# rapidshark-lipo-sensor-mk-2_1.net
KiCad netlist of a schematic drawn in EAGLE
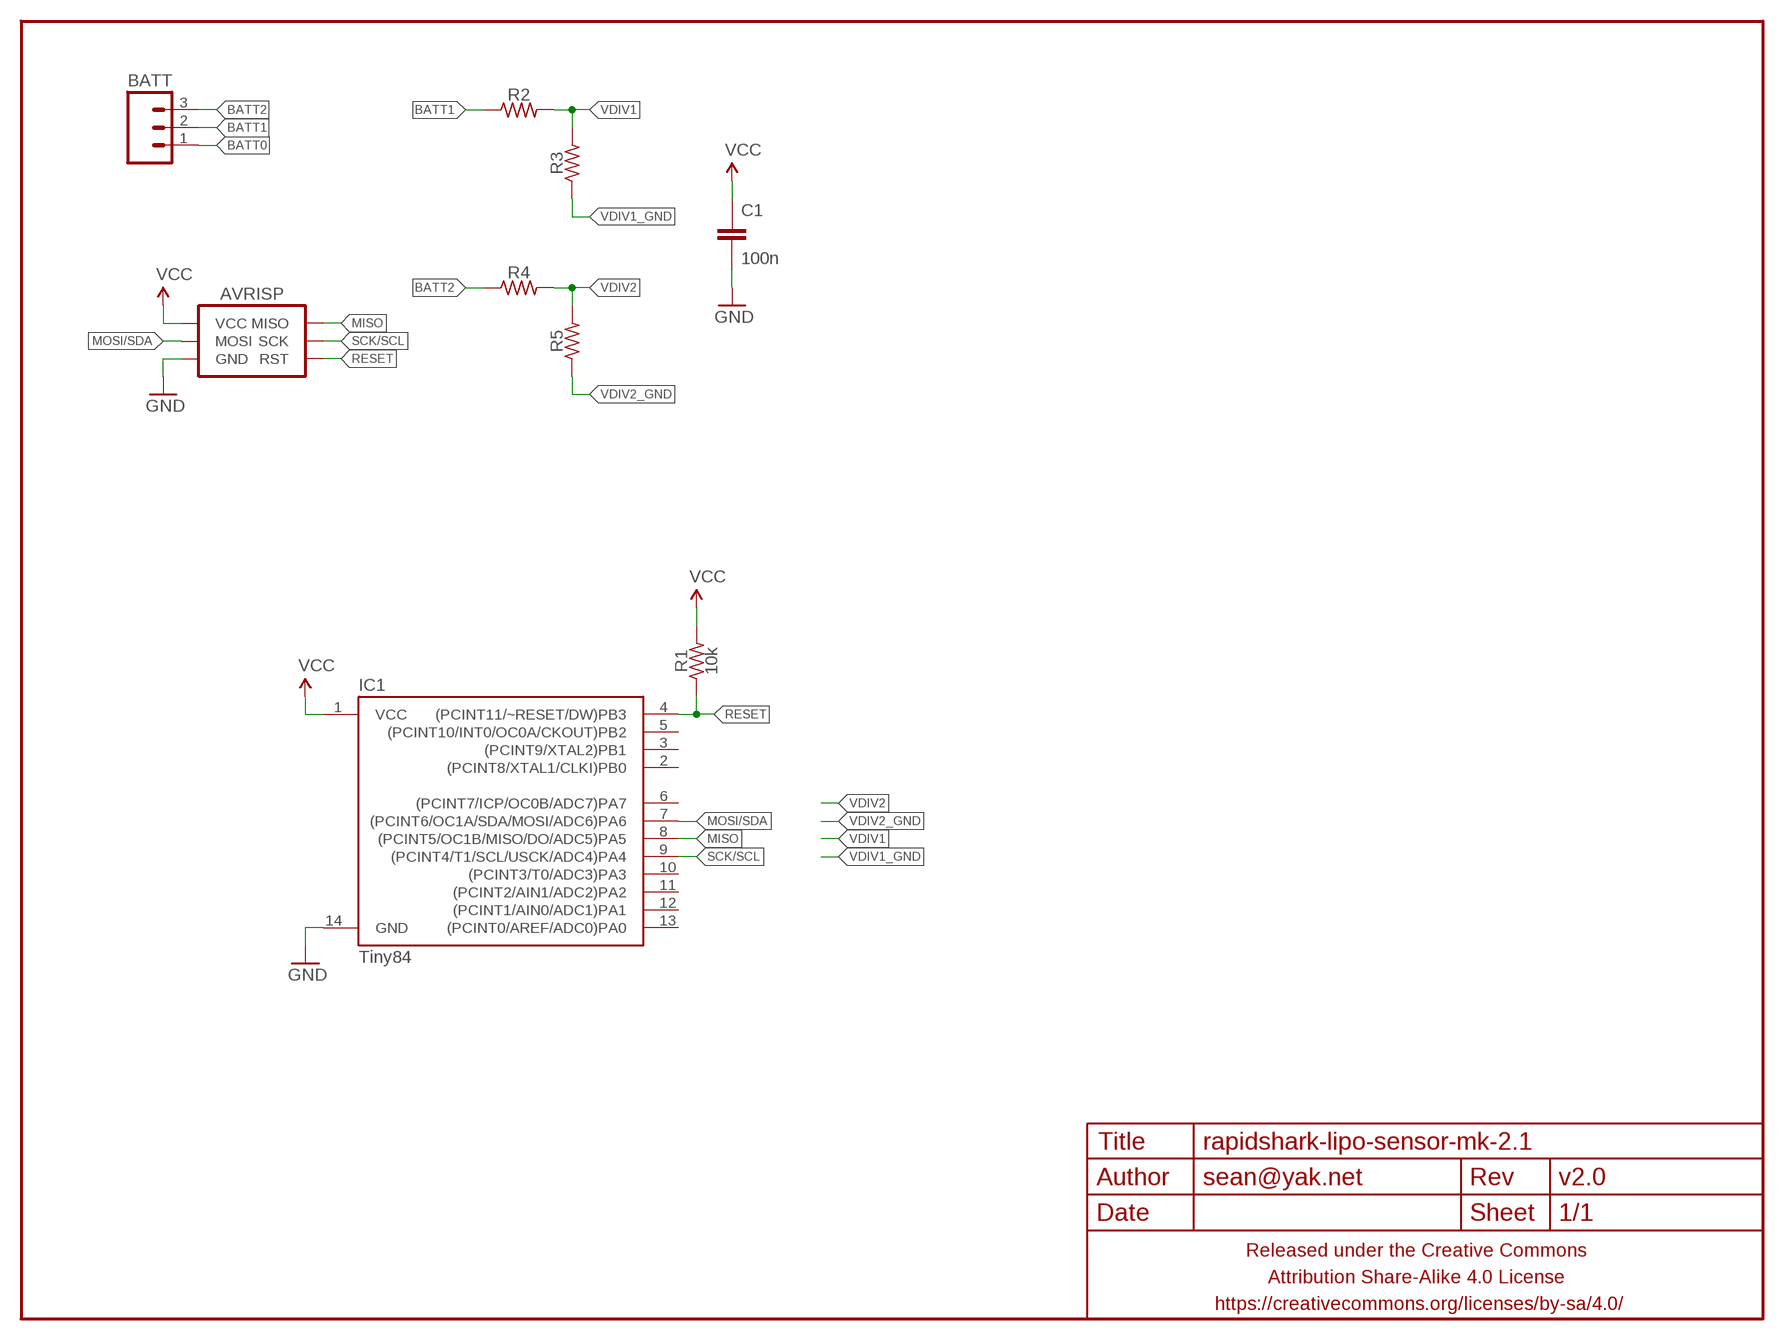
[diagram p0: schematic, sheet 1]

(export (version "E")
  (design (tool "Eeschema 10.0.6"))
  (components
    (comp (ref "AVRISP")
      (value "AVR_SPI_PRG_6PTH_INLINE_I2C")
      (footprint "eagle-import:AVR_ISP_INLINE_PTH_I2C")
      (libsource (lib "eagle-import") (part "AVR_SPI_PRG_6PTH_INLINE_I2C"))
    )
    (comp (ref "BATT")
      (value "M03PTH-CENTERED")
      (footprint "eagle-import:1X03-CENTERED")
      (libsource (lib "eagle-import") (part "M03PTH-CENTERED"))
    )
    (comp (ref "C1")
      (value "100n")
      (footprint "eagle-import:C025-024X044")
      (libsource (lib "eagle-import") (part "CAPACITOR-CERAMIC025-024X044"))
    )
    (comp (ref "FRAME1")
      (value "FRAME-LETTERNO_PACKAGE")
      (footprint "eagle-import:DUMMY")
      (fields (field (name "DESIGNER") "sean@yak.net") (field (name "VERSION") "v2.0"))
      (libsource (lib "eagle-import") (part "FRAME-LETTERNO_PACKAGE"))
    )
    (comp (ref "IC1")
      (value "Tiny84")
      (footprint "eagle-import:DIL14")
      (libsource (lib "eagle-import") (part "ATTINY84ATTINY84-20PU"))
    )
    (comp (ref "R1")
      (value "10k")
      (footprint "eagle-import:RESISTOR-AXIAL-PTH-5.08MM")
      (libsource (lib "eagle-import") (part "RESISTORPTH-AXIAL-5.08MM"))
    )
    (comp (ref "R2")
      (value "RESISTORPTH-AXIAL-5.08MM")
      (footprint "eagle-import:RESISTOR-AXIAL-PTH-5.08MM")
      (libsource (lib "eagle-import") (part "RESISTORPTH-AXIAL-5.08MM"))
    )
    (comp (ref "R3")
      (value "RESISTORPTH-AXIAL-5.08MM")
      (footprint "eagle-import:RESISTOR-AXIAL-PTH-5.08MM")
      (libsource (lib "eagle-import") (part "RESISTORPTH-AXIAL-5.08MM"))
    )
    (comp (ref "R4")
      (value "RESISTORPTH-AXIAL-5.08MM")
      (footprint "eagle-import:RESISTOR-AXIAL-PTH-5.08MM")
      (libsource (lib "eagle-import") (part "RESISTORPTH-AXIAL-5.08MM"))
    )
    (comp (ref "R5")
      (value "RESISTORPTH-AXIAL-5.08MM")
      (footprint "eagle-import:RESISTOR-AXIAL-PTH-5.08MM")
      (libsource (lib "eagle-import") (part "RESISTORPTH-AXIAL-5.08MM"))
    )
  )
  (nets
    (net (code "1") (name "BATT0") (class "Default")
      (node (ref "BATT") (pin "1") (pinfunction "1_1") (pintype "passive"))
    )
    (net (code "2") (name "BATT1") (class "Default")
      (node (ref "BATT") (pin "2") (pinfunction "2_2") (pintype "passive"))
      (node (ref "R2") (pin "P$1") (pinfunction "1_P$1") (pintype "passive"))
    )
    (net (code "3") (name "BATT2") (class "Default")
      (node (ref "BATT") (pin "3") (pinfunction "3_3") (pintype "passive"))
      (node (ref "R4") (pin "P$1") (pinfunction "1_P$1") (pintype "passive"))
    )
    (net (code "4") (name "GND") (class "Default")
      (node (ref "AVRISP") (pin "GND") (pinfunction "GND_GND") (pintype "passive"))
      (node (ref "C1") (pin "2") (pinfunction "2_2") (pintype "passive"))
      (node (ref "IC1") (pin "14") (pinfunction "GND_14") (pintype "bidirectional"))
    )
    (net (code "5") (name "MISO") (class "Default")
      (node (ref "AVRISP") (pin "MISO") (pinfunction "MISO_MISO") (pintype "passive"))
      (node (ref "IC1") (pin "8") (pinfunction "(PCINT5/OC1B/MISO/DO/ADC5)PA5_8") (pintype "bidirectional"))
    )
    (net (code "6") (name "MOSI{slash}SDA") (class "Default")
      (node (ref "AVRISP") (pin "MOSI") (pinfunction "MOSI_MOSI") (pintype "passive"))
      (node (ref "IC1") (pin "7") (pinfunction "(PCINT6/OC1A/SDA/MOSI/ADC6)PA6_7") (pintype "bidirectional"))
    )
    (net (code "7") (name "RESET") (class "Default")
      (node (ref "AVRISP") (pin "RESET") (pinfunction "RST_RESET") (pintype "passive"))
      (node (ref "IC1") (pin "4") (pinfunction "(PCINT11/~{RESET/DW})PB3_4") (pintype "bidirectional"))
      (node (ref "R1") (pin "P$1") (pinfunction "1_P$1") (pintype "passive"))
    )
    (net (code "8") (name "SCK{slash}SCL") (class "Default")
      (node (ref "AVRISP") (pin "SCK") (pinfunction "SCK_SCK") (pintype "passive"))
      (node (ref "IC1") (pin "9") (pinfunction "(PCINT4/T1/SCL/USCK/ADC4)PA4_9") (pintype "bidirectional"))
    )
    (net (code "9") (name "VCC") (class "Default")
      (node (ref "AVRISP") (pin "VCC") (pinfunction "VCC_VCC") (pintype "passive"))
      (node (ref "C1") (pin "1") (pinfunction "1_1") (pintype "passive"))
      (node (ref "IC1") (pin "1") (pinfunction "VCC_1") (pintype "bidirectional"))
      (node (ref "R1") (pin "P$2") (pinfunction "2_P$2") (pintype "passive"))
    )
    (net (code "10") (name "VDIV1") (class "Default")
      (node (ref "R2") (pin "P$2") (pinfunction "2_P$2") (pintype "passive"))
      (node (ref "R3") (pin "P$2") (pinfunction "2_P$2") (pintype "passive"))
    )
    (net (code "11") (name "VDIV1_GND") (class "Default")
      (node (ref "R3") (pin "P$1") (pinfunction "1_P$1") (pintype "passive"))
    )
    (net (code "12") (name "VDIV2") (class "Default")
      (node (ref "R4") (pin "P$2") (pinfunction "2_P$2") (pintype "passive"))
      (node (ref "R5") (pin "P$2") (pinfunction "2_P$2") (pintype "passive"))
    )
    (net (code "13") (name "VDIV2_GND") (class "Default")
      (node (ref "R5") (pin "P$1") (pinfunction "1_P$1") (pintype "passive"))
    )
    (net (code "14") (name "unconnected-(IC1-(PCINT0{slash}AREF{slash}ADC0)PA0-Pad13)") (class "Default")
      (node (ref "IC1") (pin "13") (pinfunction "(PCINT0/AREF/ADC0)PA0_13") (pintype "bidirectional"))
    )
    (net (code "15") (name "unconnected-(IC1-(PCINT1{slash}AIN0{slash}ADC1)PA1-Pad12)") (class "Default")
      (node (ref "IC1") (pin "12") (pinfunction "(PCINT1/AIN0/ADC1)PA1_12") (pintype "bidirectional"))
    )
    (net (code "16") (name "unconnected-(IC1-(PCINT2{slash}AIN1{slash}ADC2)PA2-Pad11)") (class "Default")
      (node (ref "IC1") (pin "11") (pinfunction "(PCINT2/AIN1/ADC2)PA2_11") (pintype "bidirectional"))
    )
    (net (code "17") (name "unconnected-(IC1-(PCINT3{slash}T0{slash}ADC3)PA3-Pad10)") (class "Default")
      (node (ref "IC1") (pin "10") (pinfunction "(PCINT3/T0/ADC3)PA3_10") (pintype "bidirectional"))
    )
    (net (code "18") (name "unconnected-(IC1-(PCINT7{slash}ICP{slash}OC0B{slash}ADC7)PA7-Pad6)") (class "Default")
      (node (ref "IC1") (pin "6") (pinfunction "(PCINT7/ICP/OC0B/ADC7)PA7_6") (pintype "bidirectional"))
    )
    (net (code "19") (name "unconnected-(IC1-(PCINT8{slash}XTAL1{slash}CLKI)PB0-Pad2)") (class "Default")
      (node (ref "IC1") (pin "2") (pinfunction "(PCINT8/XTAL1/CLKI)PB0_2") (pintype "bidirectional"))
    )
    (net (code "20") (name "unconnected-(IC1-(PCINT9{slash}XTAL2)PB1-Pad3)") (class "Default")
      (node (ref "IC1") (pin "3") (pinfunction "(PCINT9/XTAL2)PB1_3") (pintype "bidirectional"))
    )
    (net (code "21") (name "unconnected-(IC1-(PCINT10{slash}INT0{slash}OC0A{slash}CKOUT)PB2-Pad5)") (class "Default")
      (node (ref "IC1") (pin "5") (pinfunction "(PCINT10/INT0/OC0A/CKOUT)PB2_5") (pintype "bidirectional"))
    )
  )
)
